# design.net
KiCad netlist of a schematic drawn in Altium Designer
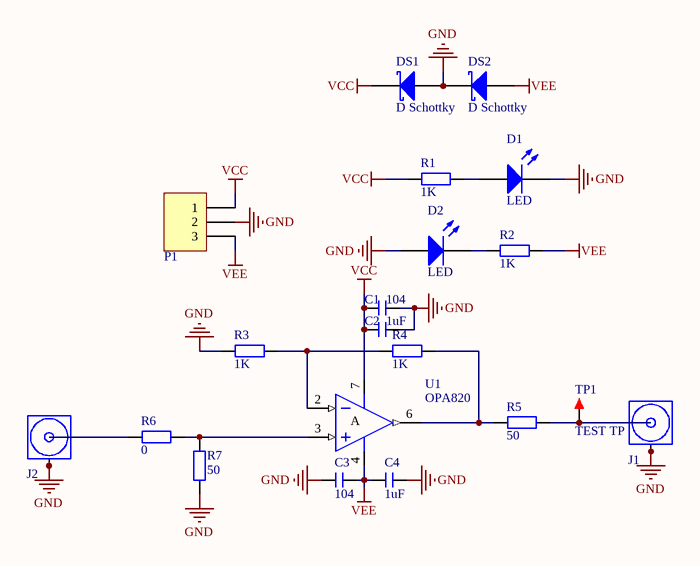
[diagram p0: 同向放大器.SchDoc]

(export (version "E")
  (design (tool "Eeschema 10.0.6"))
  (components
    (comp (ref "C1")
      (value "104")
      (footprint "C 0603")
      (description "无极性贴片电容")
      (fields (field (name "版权归属") "源创客"))
      (libsource (lib "电阻-电容-电感") (part "C"))
    )
    (comp (ref "C2")
      (value "1uF")
      (footprint "C 0603")
      (description "无极性贴片电容")
      (fields (field (name "版权归属") "源创客"))
      (libsource (lib "电阻-电容-电感") (part "C"))
    )
    (comp (ref "C3")
      (value "104")
      (footprint "C 0603")
      (description "无极性贴片电容")
      (fields (field (name "版权归属") "源创客"))
      (libsource (lib "电阻-电容-电感") (part "C"))
    )
    (comp (ref "C4")
      (value "1uF")
      (footprint "C 0603")
      (description "无极性贴片电容")
      (fields (field (name "版权归属") "源创客"))
      (libsource (lib "电阻-电容-电感") (part "C"))
    )
    (comp (ref "D1")
      (value "LED")
      (footprint "LED_0805")
      (description "发光二极管")
      (fields (field (name "PUBLISHER") "Altium Limited"))
      (libsource (lib "LIB") (part "LED"))
    )
    (comp (ref "D2")
      (value "LED")
      (footprint "LED_0805")
      (description "发光二极管")
      (fields (field (name "PUBLISHER") "Altium Limited"))
      (libsource (lib "LIB") (part "LED"))
    )
    (comp (ref "DS1")
      (value "D Schottky")
      (footprint "DIODE-SMA")
      (description "Schottky Diode")
      (fields (field (name "PUBLISHER") "Altium Limited"))
      (libsource (lib "LIB") (part "D Schottky"))
    )
    (comp (ref "DS2")
      (value "D Schottky")
      (footprint "DIODE-SMA")
      (description "Schottky Diode")
      (fields (field (name "PUBLISHER") "Altium Limited"))
      (libsource (lib "LIB") (part "D Schottky"))
    )
    (comp (ref "J1") (value "COAX") (footprint "MCX5.08-5-H") (libsource (lib "LIB") (part "COAX")))
    (comp (ref "J2") (value "COAX") (footprint "MCX5.08-5-H") (libsource (lib "LIB") (part "COAX")))
    (comp (ref "P1")
      (value "Header 3")
      (footprint "HDR3X1_B2")
      (description "接插件")
      (fields (field (name "PUBLISHER") "Altium Limited"))
      (libsource (lib "LIB") (part "Header 3"))
    )
    (comp (ref "R1")
      (value "1K")
      (footprint "R 0805")
      (description "贴片电阻")
      (fields (field (name "版权归属") "源创客"))
      (libsource (lib "电阻-电容-电感") (part "R"))
    )
    (comp (ref "R2")
      (value "1K")
      (footprint "R 0805")
      (description "贴片电阻")
      (fields (field (name "版权归属") "源创客"))
      (libsource (lib "电阻-电容-电感") (part "R"))
    )
    (comp (ref "R3")
      (value "1K")
      (footprint "R 0603")
      (description "贴片电阻")
      (fields (field (name "版权归属") "源创客"))
      (libsource (lib "电阻-电容-电感") (part "R"))
    )
    (comp (ref "R4")
      (value "1K")
      (footprint "R 0603")
      (description "贴片电阻")
      (fields (field (name "版权归属") "源创客"))
      (libsource (lib "电阻-电容-电感") (part "R"))
    )
    (comp (ref "R5")
      (value "50")
      (footprint "R 0603")
      (description "贴片电阻")
      (fields (field (name "版权归属") "源创客"))
      (libsource (lib "电阻-电容-电感") (part "R"))
    )
    (comp (ref "R6")
      (value "0")
      (footprint "R 0603")
      (description "贴片电阻")
      (fields (field (name "版权归属") "源创客"))
      (libsource (lib "电阻-电容-电感") (part "R"))
    )
    (comp (ref "R7")
      (value "50")
      (footprint "R 0603")
      (description "贴片电阻")
      (fields (field (name "版权归属") "源创客"))
      (libsource (lib "电阻-电容-电感") (part "R"))
    )
    (comp (ref "TP1")
      (value "TEST TP")
      (footprint "TEST TP1.4_B")
      (description "测试环")
      (fields (field (name "版权归属") "源创客"))
      (libsource (lib "未分类器件") (part "TEST TP"))
    )
    (comp (ref "U1")
      (value "OPA820")
      (footprint "SOIC8_N")
      (description "单位增益稳定低噪声电压反馈运算放大器")
      (libsource (lib "LIB") (part "OPA820"))
    )
  )
  (nets
    (net (code "1") (name "GND") (class "Default")
      (node (ref "C1") (pin "1") (pinfunction "1_1") (pintype "passive"))
      (node (ref "C2") (pin "1") (pinfunction "1_1") (pintype "passive"))
      (node (ref "C3") (pin "2") (pinfunction "2_2") (pintype "passive"))
      (node (ref "C4") (pin "1") (pinfunction "1_1") (pintype "passive"))
      (node (ref "D1") (pin "2") (pinfunction "K_2") (pintype "passive"))
      (node (ref "D2") (pin "1") (pinfunction "A_1") (pintype "passive"))
      (node (ref "DS1") (pin "1") (pinfunction "1_1") (pintype "passive"))
      (node (ref "DS2") (pin "2") (pinfunction "2_2") (pintype "passive"))
      (node (ref "J1") (pin "2") (pinfunction "GND_2") (pintype "passive"))
      (node (ref "J1") (pin "3") (pinfunction "GND_3") (pintype "passive"))
      (node (ref "J1") (pin "4") (pinfunction "GND_4") (pintype "passive"))
      (node (ref "J1") (pin "5") (pinfunction "GND_5") (pintype "passive"))
      (node (ref "J2") (pin "2") (pinfunction "GND_2") (pintype "passive"))
      (node (ref "J2") (pin "3") (pinfunction "GND_3") (pintype "passive"))
      (node (ref "J2") (pin "4") (pinfunction "GND_4") (pintype "passive"))
      (node (ref "J2") (pin "5") (pinfunction "GND_5") (pintype "passive"))
      (node (ref "P1") (pin "2") (pinfunction "2_2") (pintype "passive"))
      (node (ref "R3") (pin "1") (pinfunction "1_1") (pintype "passive"))
      (node (ref "R7") (pin "1") (pinfunction "1_1") (pintype "passive"))
    )
    (net (code "2") (name "Net-(D1-A)") (class "Default")
      (node (ref "D1") (pin "1") (pinfunction "A_1") (pintype "passive"))
      (node (ref "R1") (pin "2") (pinfunction "2_2") (pintype "passive"))
    )
    (net (code "3") (name "Net-(D2-K)") (class "Default")
      (node (ref "D2") (pin "2") (pinfunction "K_2") (pintype "passive"))
      (node (ref "R2") (pin "1") (pinfunction "1_1") (pintype "passive"))
    )
    (net (code "4") (name "Net-(J1-Signal)") (class "Default")
      (node (ref "J1") (pin "1") (pinfunction "Signal_1") (pintype "passive"))
      (node (ref "R5") (pin "2") (pinfunction "2_2") (pintype "passive"))
      (node (ref "TP1") (pin "1") (pinfunction "1_1") (pintype "passive"))
    )
    (net (code "5") (name "Net-(J2-Signal)") (class "Default")
      (node (ref "J2") (pin "1") (pinfunction "Signal_1") (pintype "passive"))
      (node (ref "R6") (pin "2") (pinfunction "2_2") (pintype "passive"))
    )
    (net (code "6") (name "Net-(U1-+IN)") (class "Default")
      (node (ref "R6") (pin "1") (pinfunction "1_1") (pintype "passive"))
      (node (ref "R7") (pin "2") (pinfunction "2_2") (pintype "passive"))
      (node (ref "U1") (pin "3") (pinfunction "+IN_3") (pintype "input"))
    )
    (net (code "7") (name "Net-(U1--IN)") (class "Default")
      (node (ref "R3") (pin "2") (pinfunction "2_2") (pintype "passive"))
      (node (ref "R4") (pin "1") (pinfunction "1_1") (pintype "passive"))
      (node (ref "U1") (pin "2") (pinfunction "-IN_2") (pintype "input"))
    )
    (net (code "8") (name "Net-(U1-OUT)") (class "Default")
      (node (ref "R4") (pin "2") (pinfunction "2_2") (pintype "passive"))
      (node (ref "R5") (pin "1") (pinfunction "1_1") (pintype "passive"))
      (node (ref "U1") (pin "6") (pinfunction "OUT_6") (pintype "output"))
    )
    (net (code "9") (name "VCC") (class "Default")
      (node (ref "C1") (pin "2") (pinfunction "2_2") (pintype "passive"))
      (node (ref "C2") (pin "2") (pinfunction "2_2") (pintype "passive"))
      (node (ref "DS1") (pin "2") (pinfunction "2_2") (pintype "passive"))
      (node (ref "P1") (pin "1") (pinfunction "1_1") (pintype "passive"))
      (node (ref "R1") (pin "1") (pinfunction "1_1") (pintype "passive"))
      (node (ref "U1") (pin "7") (pinfunction "V+_7") (pintype "power_in"))
    )
    (net (code "10") (name "VEE") (class "Default")
      (node (ref "C3") (pin "1") (pinfunction "1_1") (pintype "passive"))
      (node (ref "C4") (pin "2") (pinfunction "2_2") (pintype "passive"))
      (node (ref "DS2") (pin "1") (pinfunction "1_1") (pintype "passive"))
      (node (ref "P1") (pin "3") (pinfunction "3_3") (pintype "passive"))
      (node (ref "R2") (pin "2") (pinfunction "2_2") (pintype "passive"))
      (node (ref "U1") (pin "4") (pinfunction "V-_4") (pintype "power_in"))
    )
  )
)
